# DummyLoad.net
KiCad netlist of a schematic drawn in EAGLE
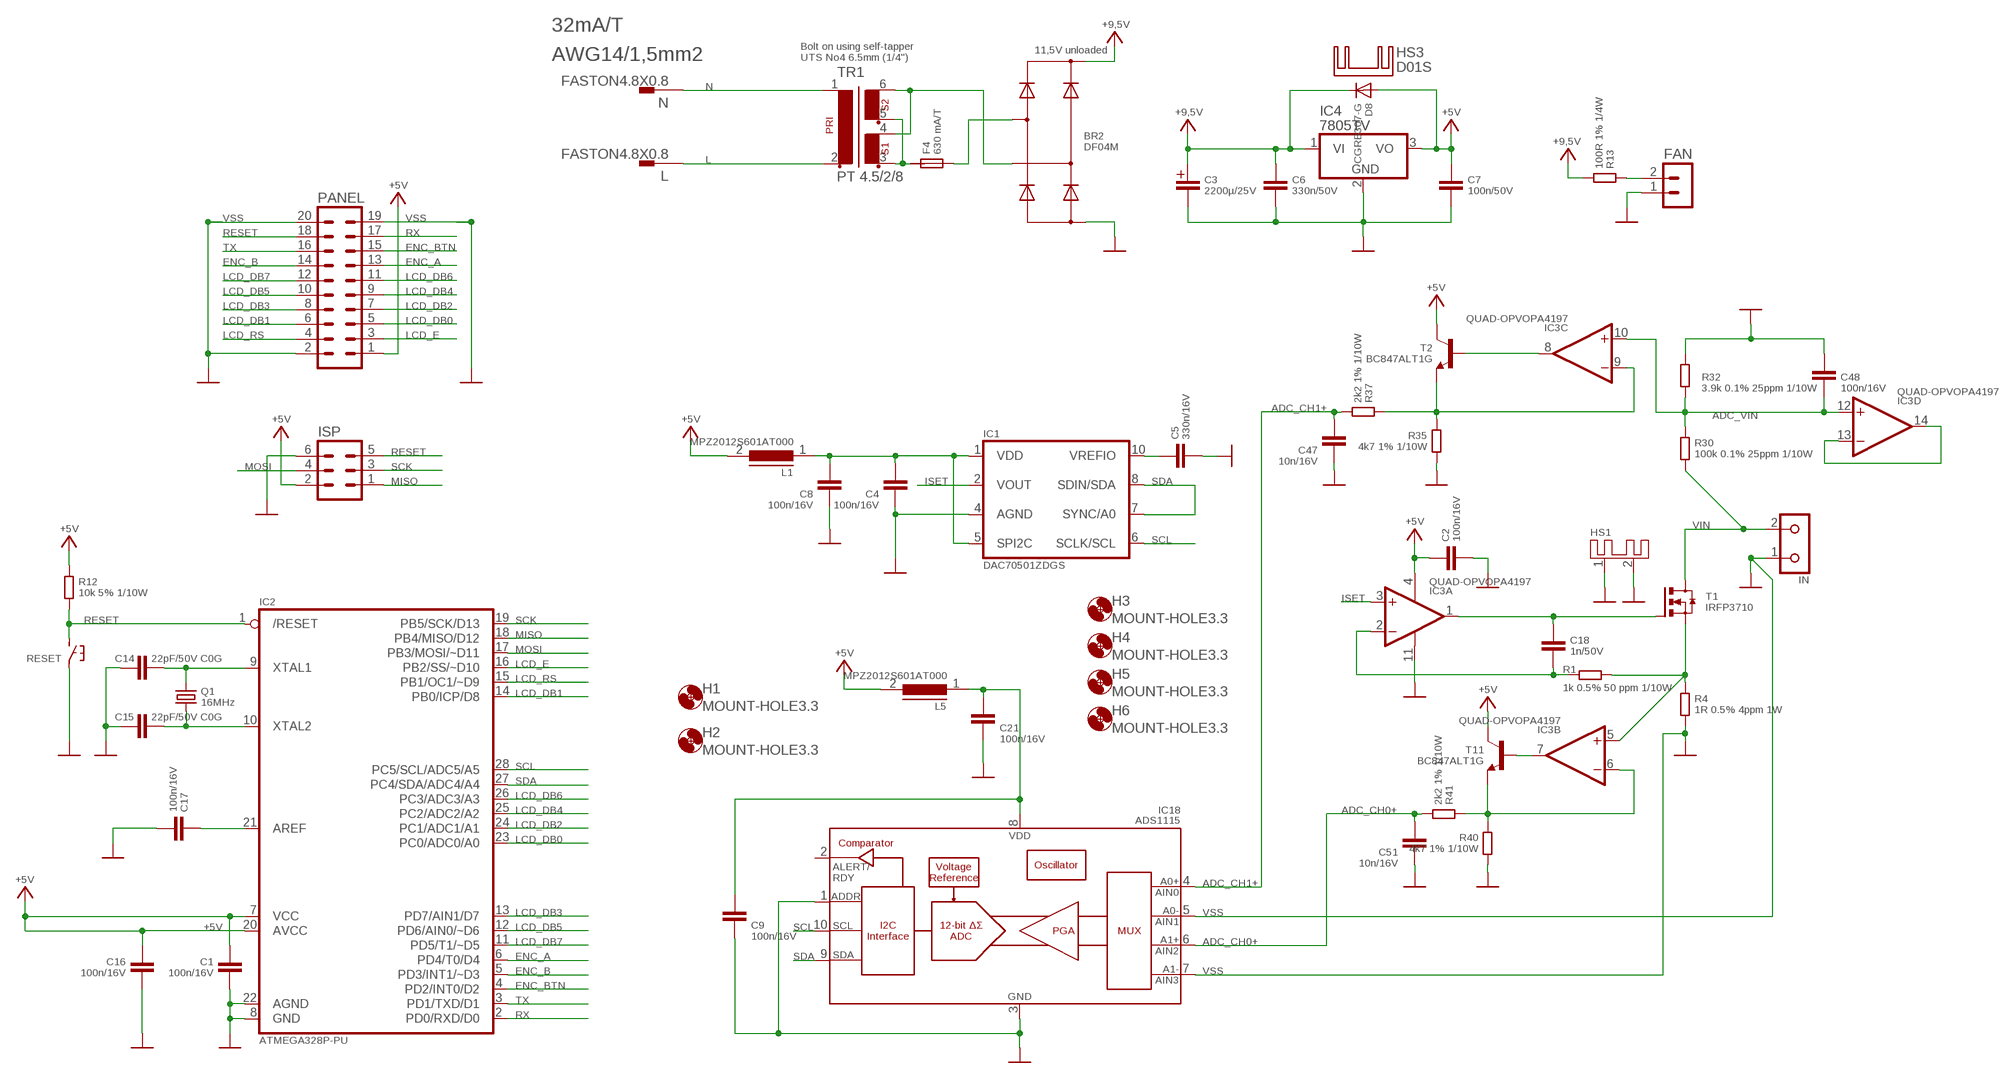
[diagram p0: schematic, sheet 1]

(export (version "E")
  (design (tool "Eeschema 10.0.6"))
  (components
    (comp (ref "BR2")
      (value "DF04M")
      (footprint "eagle-import:BR-DIL2")
      (libsource (lib "eagle-import") (part "BRDIL2"))
    )
    (comp (ref "C1")
      (value "100n/16V")
      (footprint "eagle-import:0805")
      (libsource (lib "eagle-import") (part "CC/0805"))
    )
    (comp (ref "C2")
      (value "100n/16V")
      (footprint "eagle-import:0805")
      (libsource (lib "eagle-import") (part "CC/0805"))
    )
    (comp (ref "C3")
      (value "2200µ/25V")
      (footprint "eagle-import:C+_5_12.5")
      (libsource (lib "eagle-import") (part "C+5/12.5"))
    )
    (comp (ref "C4")
      (value "100n/16V")
      (footprint "eagle-import:0805")
      (libsource (lib "eagle-import") (part "CC/0805"))
    )
    (comp (ref "C5")
      (value "330n/16V")
      (footprint "eagle-import:0805")
      (libsource (lib "eagle-import") (part "CC/0805"))
    )
    (comp (ref "C6")
      (value "330n/50V")
      (footprint "eagle-import:0805")
      (libsource (lib "eagle-import") (part "CC/0805"))
    )
    (comp (ref "C7")
      (value "100n/50V")
      (footprint "eagle-import:0805")
      (libsource (lib "eagle-import") (part "CC/0805"))
    )
    (comp (ref "C8")
      (value "100n/16V")
      (footprint "eagle-import:0805")
      (libsource (lib "eagle-import") (part "CC/0805"))
    )
    (comp (ref "C9")
      (value "100n/16V")
      (footprint "eagle-import:0805")
      (libsource (lib "eagle-import") (part "CC/0805"))
    )
    (comp (ref "C14")
      (value "22pF/50V C0G")
      (footprint "eagle-import:0805")
      (libsource (lib "eagle-import") (part "CC/0805"))
    )
    (comp (ref "C15")
      (value "22pF/50V C0G")
      (footprint "eagle-import:0805")
      (libsource (lib "eagle-import") (part "CC/0805"))
    )
    (comp (ref "C16")
      (value "100n/16V")
      (footprint "eagle-import:0805")
      (libsource (lib "eagle-import") (part "CC/0805"))
    )
    (comp (ref "C17")
      (value "100n/16V")
      (footprint "eagle-import:0805")
      (libsource (lib "eagle-import") (part "CC/0805"))
    )
    (comp (ref "C18")
      (value "1n/50V")
      (footprint "eagle-import:0805")
      (libsource (lib "eagle-import") (part "CC/0805"))
    )
    (comp (ref "C21")
      (value "100n/16V")
      (footprint "eagle-import:0805")
      (libsource (lib "eagle-import") (part "CC/0805"))
    )
    (comp (ref "C47")
      (value "10n/16V")
      (footprint "eagle-import:0805")
      (libsource (lib "eagle-import") (part "CC/0805"))
    )
    (comp (ref "C48")
      (value "100n/16V")
      (footprint "eagle-import:0805")
      (libsource (lib "eagle-import") (part "CC/0805"))
    )
    (comp (ref "C51")
      (value "10n/16V")
      (footprint "eagle-import:0805")
      (libsource (lib "eagle-import") (part "CC/0805"))
    )
    (comp (ref "D8")
      (value "CGRB307-G")
      (footprint "eagle-import:DO214AA-CGRB307-G")
      (libsource (lib "eagle-import") (part "DWIDE"))
    )
    (comp (ref "F4")
      (value "630 mA/T")
      (footprint "eagle-import:F5X20")
      (libsource (lib "eagle-import") (part "F5X20"))
    )
    (comp (ref "FAN")
      (value "JST-PH-2.0-2P")
      (footprint "eagle-import:JST-PH-2.0-2P")
      (libsource (lib "eagle-import") (part "JST-PH-2.0-2P"))
    )
    (comp (ref "H1")
      (value "MOUNT-HOLE3.3")
      (footprint "eagle-import:3,3")
      (libsource (lib "eagle-import") (part "MOUNT-HOLE3.3"))
    )
    (comp (ref "H2")
      (value "MOUNT-HOLE3.3")
      (footprint "eagle-import:3,3")
      (libsource (lib "eagle-import") (part "MOUNT-HOLE3.3"))
    )
    (comp (ref "H3")
      (value "MOUNT-HOLE3.3")
      (footprint "eagle-import:3,3")
      (libsource (lib "eagle-import") (part "MOUNT-HOLE3.3"))
    )
    (comp (ref "H4")
      (value "MOUNT-HOLE3.3")
      (footprint "eagle-import:3,3")
      (libsource (lib "eagle-import") (part "MOUNT-HOLE3.3"))
    )
    (comp (ref "H5")
      (value "MOUNT-HOLE3.3")
      (footprint "eagle-import:3,3")
      (libsource (lib "eagle-import") (part "MOUNT-HOLE3.3"))
    )
    (comp (ref "H6")
      (value "MOUNT-HOLE3.3")
      (footprint "eagle-import:3,3")
      (libsource (lib "eagle-import") (part "MOUNT-HOLE3.3"))
    )
    (comp (ref "HS1")
      (value "HSCR201-50")
      (footprint "eagle-import:CR201-50")
      (libsource (lib "eagle-import") (part "HSCR201-50"))
    )
    (comp (ref "HS3")
      (value "D01S")
      (footprint "eagle-import:D01S")
      (libsource (lib "eagle-import") (part "D01S"))
    )
    (comp (ref "IC1")
      (value "DAC70501ZDGS")
      (footprint "eagle-import:VSSOP10")
      (libsource (lib "eagle-import") (part "DAC70501"))
    )
    (comp (ref "IC2")
      (value "ATMEGA328P-PU")
      (footprint "eagle-import:DIL28")
      (libsource (lib "eagle-import") (part "ATMEGA328P-PU"))
    )
    (comp (ref "IC3")
      (value "QUAD-OPVOPA4197")
      (footprint "eagle-import:SO14")
      (fields (field (name "OC_MOUSER") "595-OPA4197IDR"))
      (libsource (lib "eagle-import") (part "QUAD-OPVOPA4197"))
    )
    (comp (ref "IC4")
      (value "7805TV")
      (footprint "eagle-import:TO220V")
      (libsource (lib "eagle-import") (part "78TV05"))
    )
    (comp (ref "IC18")
      (value "ADS1115")
      (footprint "eagle-import:VSSOP10")
      (libsource (lib "eagle-import") (part "ADS1015VSSOP10"))
    )
    (comp (ref "IN")
      (value "KL2691311500002")
      (footprint "eagle-import:KL2-691311500002")
      (libsource (lib "eagle-import") (part "KL2691311500002"))
    )
    (comp (ref "ISP")
      (value "ML6")
      (footprint "eagle-import:ML6")
      (libsource (lib "eagle-import") (part "ML6"))
    )
    (comp (ref "L")
      (value "FASTON4.8X0.8")
      (footprint "eagle-import:FASTON-4.8X0.8")
      (libsource (lib "eagle-import") (part "FASTON4.8X0.8"))
    )
    (comp (ref "L1")
      (value "MPZ2012S601AT000")
      (footprint "eagle-import:C0805K")
      (libsource (lib "eagle-import") (part "L0805"))
    )
    (comp (ref "L5")
      (value "MPZ2012S601AT000")
      (footprint "eagle-import:C0805K")
      (libsource (lib "eagle-import") (part "L0805"))
    )
    (comp (ref "N")
      (value "FASTON4.8X0.8")
      (footprint "eagle-import:FASTON-4.8X0.8")
      (libsource (lib "eagle-import") (part "FASTON4.8X0.8"))
    )
    (comp (ref "PANEL")
      (value "MA10-2")
      (footprint "eagle-import:MA10-2")
      (libsource (lib "eagle-import") (part "MA10-2"))
    )
    (comp (ref "Q1")
      (value "16MHz")
      (footprint "eagle-import:Q-5X3.2MM-TXC-7A.SERIES")
      (libsource (lib "eagle-import") (part "Q5X3.2MM-TXC-7A-SERIES"))
    )
    (comp (ref "R1")
      (value "1k 0.5% 50 ppm 1/10W")
      (footprint "eagle-import:C0805K")
      (libsource (lib "eagle-import") (part "R-SMD0805"))
    )
    (comp (ref "R4")
      (value "1R 0.5% 4ppm 1W")
      (footprint "eagle-import:R-SHUNT-VSR")
      (libsource (lib "eagle-import") (part "R-SHUNTVSR"))
    )
    (comp (ref "R12")
      (value "10k 5% 1/10W")
      (footprint "eagle-import:C0805K")
      (libsource (lib "eagle-import") (part "R-SMD0805"))
    )
    (comp (ref "R13")
      (value "100R 1% 1/4W")
      (footprint "eagle-import:C0805K")
      (libsource (lib "eagle-import") (part "R-SMD0805"))
    )
    (comp (ref "R30")
      (value "100k 0.1% 25ppm 1/10W")
      (footprint "eagle-import:C0805K")
      (libsource (lib "eagle-import") (part "R-SMD0805"))
    )
    (comp (ref "R32")
      (value "3.9k 0.1% 25ppm 1/10W")
      (footprint "eagle-import:C0805K")
      (libsource (lib "eagle-import") (part "R-SMD0805"))
    )
    (comp (ref "R35")
      (value "4k7 1% 1/10W")
      (footprint "eagle-import:C0805K")
      (libsource (lib "eagle-import") (part "R-SMD0805"))
    )
    (comp (ref "R37")
      (value "2k2 1% 1/10W")
      (footprint "eagle-import:C0805K")
      (libsource (lib "eagle-import") (part "R-SMD0805"))
    )
    (comp (ref "R40")
      (value "4k7 1% 1/10W")
      (footprint "eagle-import:C0805K")
      (libsource (lib "eagle-import") (part "R-SMD0805"))
    )
    (comp (ref "R41")
      (value "2k2 1% 1/10W")
      (footprint "eagle-import:C0805K")
      (libsource (lib "eagle-import") (part "R-SMD0805"))
    )
    (comp (ref "RESET")
      (value "TS1B3F-10XX")
      (footprint "eagle-import:B3F-10XX")
      (libsource (lib "eagle-import") (part "TS1B3F-10XX"))
    )
    (comp (ref "T1")
      (value "IRFP3710")
      (footprint "eagle-import:TOP3AV")
      (libsource (lib "eagle-import") (part "T-NMOSTO247"))
    )
    (comp (ref "T2")
      (value "BC847ALT1G")
      (footprint "eagle-import:SOT23-BEC")
      (libsource (lib "eagle-import") (part "T-NPNSOT23-BEC"))
    )
    (comp (ref "T11")
      (value "BC847ALT1G")
      (footprint "eagle-import:SOT23-BEC")
      (libsource (lib "eagle-import") (part "T-NPNSOT23-BEC"))
    )
    (comp (ref "TR1")
      (value "PT 4.5/2/8")
      (footprint "eagle-import:PT_4,5_2_..")
      (libsource (lib "eagle-import") (part "PT4,5/2/.."))
    )
  )
  (nets
    (net (code "1") (name "+5V") (class "Default")
      (node (ref "C1") (pin "1") (pinfunction "1_1") (pintype "passive"))
      (node (ref "C16") (pin "1") (pinfunction "1_1") (pintype "passive"))
      (node (ref "C2") (pin "1") (pinfunction "1_1") (pintype "passive"))
      (node (ref "C7") (pin "1") (pinfunction "1_1") (pintype "passive"))
      (node (ref "D8") (pin "A") (pinfunction "A_A") (pintype "passive"))
      (node (ref "IC2") (pin "20") (pinfunction "AVCC_20") (pintype "power_in"))
      (node (ref "IC2") (pin "7") (pinfunction "VCC_7") (pintype "power_in"))
      (node (ref "IC3") (pin "4") (pinfunction "V+_4") (pintype "power_in"))
      (node (ref "IC4") (pin "3") (pinfunction "VO_3") (pintype "passive"))
      (node (ref "ISP") (pin "2") (pinfunction "2_2") (pintype "passive"))
      (node (ref "L1") (pin "2") (pinfunction "2_2") (pintype "passive"))
      (node (ref "L5") (pin "2") (pinfunction "2_2") (pintype "passive"))
      (node (ref "PANEL") (pin "1") (pinfunction "1_1") (pintype "passive"))
      (node (ref "R12") (pin "1") (pinfunction "1_1") (pintype "passive"))
      (node (ref "T11") (pin "C") (pinfunction "C_C") (pintype "passive"))
      (node (ref "T2") (pin "C") (pinfunction "C_C") (pintype "passive"))
    )
    (net (code "2") (name "+9,5V") (class "Default")
      (node (ref "BR2") (pin "DC+") (pinfunction "DC+_DC+") (pintype "passive"))
      (node (ref "C3") (pin "+") (pinfunction "+_+") (pintype "passive"))
      (node (ref "C6") (pin "1") (pinfunction "1_1") (pintype "passive"))
      (node (ref "D8") (pin "C") (pinfunction "C_C") (pintype "passive"))
      (node (ref "IC4") (pin "1") (pinfunction "VI_1") (pintype "input"))
      (node (ref "R13") (pin "2") (pinfunction "2_2") (pintype "passive"))
    )
    (net (code "3") (name "/ADC_CH0+") (class "Default")
      (node (ref "C51") (pin "1") (pinfunction "1_1") (pintype "passive"))
      (node (ref "IC18") (pin "6") (pinfunction "AIN2_6") (pintype "bidirectional"))
      (node (ref "R41") (pin "2") (pinfunction "2_2") (pintype "passive"))
    )
    (net (code "4") (name "/ADC_CH1+") (class "Default")
      (node (ref "C47") (pin "1") (pinfunction "1_1") (pintype "passive"))
      (node (ref "IC18") (pin "4") (pinfunction "AIN0_4") (pintype "bidirectional"))
      (node (ref "R37") (pin "2") (pinfunction "2_2") (pintype "passive"))
    )
    (net (code "5") (name "/ADC_VIN") (class "Default")
      (node (ref "C48") (pin "2") (pinfunction "2_2") (pintype "passive"))
      (node (ref "IC3") (pin "10") (pinfunction "+IN_10") (pintype "input"))
      (node (ref "IC3") (pin "12") (pinfunction "+IN_12") (pintype "input"))
      (node (ref "R30") (pin "1") (pinfunction "1_1") (pintype "passive"))
      (node (ref "R32") (pin "2") (pinfunction "2_2") (pintype "passive"))
    )
    (net (code "6") (name "/ENC_A") (class "Default")
      (node (ref "IC2") (pin "6") (pinfunction "PD4/T0/D4_6") (pintype "bidirectional"))
      (node (ref "PANEL") (pin "13") (pinfunction "13_13") (pintype "passive"))
    )
    (net (code "7") (name "/ENC_B") (class "Default")
      (node (ref "IC2") (pin "5") (pinfunction "PD3/INT1/~{D3}_5") (pintype "bidirectional"))
      (node (ref "PANEL") (pin "14") (pinfunction "14_14") (pintype "passive"))
    )
    (net (code "8") (name "/ENC_BTN") (class "Default")
      (node (ref "IC2") (pin "4") (pinfunction "PD2/INT0/D2_4") (pintype "bidirectional"))
      (node (ref "PANEL") (pin "15") (pinfunction "15_15") (pintype "passive"))
    )
    (net (code "9") (name "/ISET") (class "Default")
      (node (ref "IC1") (pin "2") (pinfunction "VOUT_2") (pintype "output"))
      (node (ref "IC3") (pin "3") (pinfunction "+IN_3") (pintype "input"))
    )
    (net (code "10") (name "/L") (class "Default")
      (node (ref "L") (pin "A1") (pinfunction "1_A1") (pintype "passive"))
      (node (ref "L") (pin "A2") (pinfunction "1_A2") (pintype "passive"))
      (node (ref "TR1") (pin "2") (pinfunction "2_2") (pintype "passive"))
    )
    (net (code "11") (name "/LCD_DB0") (class "Default")
      (node (ref "IC2") (pin "23") (pinfunction "PC0/ADC0/A0_23") (pintype "bidirectional"))
      (node (ref "PANEL") (pin "5") (pinfunction "5_5") (pintype "passive"))
    )
    (net (code "12") (name "/LCD_DB1") (class "Default")
      (node (ref "IC2") (pin "14") (pinfunction "PB0/ICP/D8_14") (pintype "bidirectional"))
      (node (ref "PANEL") (pin "6") (pinfunction "6_6") (pintype "passive"))
    )
    (net (code "13") (name "/LCD_DB2") (class "Default")
      (node (ref "IC2") (pin "24") (pinfunction "PC1/ADC1/A1_24") (pintype "bidirectional"))
      (node (ref "PANEL") (pin "7") (pinfunction "7_7") (pintype "passive"))
    )
    (net (code "14") (name "/LCD_DB3") (class "Default")
      (node (ref "IC2") (pin "13") (pinfunction "PD7/AIN1/D7_13") (pintype "bidirectional"))
      (node (ref "PANEL") (pin "8") (pinfunction "8_8") (pintype "passive"))
    )
    (net (code "15") (name "/LCD_DB4") (class "Default")
      (node (ref "IC2") (pin "25") (pinfunction "PC2/ADC2/A2_25") (pintype "bidirectional"))
      (node (ref "PANEL") (pin "9") (pinfunction "9_9") (pintype "passive"))
    )
    (net (code "16") (name "/LCD_DB5") (class "Default")
      (node (ref "IC2") (pin "12") (pinfunction "PD6/AIN0/~{D6}_12") (pintype "bidirectional"))
      (node (ref "PANEL") (pin "10") (pinfunction "10_10") (pintype "passive"))
    )
    (net (code "17") (name "/LCD_DB6") (class "Default")
      (node (ref "IC2") (pin "26") (pinfunction "PC3/ADC3/A3_26") (pintype "bidirectional"))
      (node (ref "PANEL") (pin "11") (pinfunction "11_11") (pintype "passive"))
    )
    (net (code "18") (name "/LCD_DB7") (class "Default")
      (node (ref "IC2") (pin "11") (pinfunction "PD5/T1/~{D5}_11") (pintype "bidirectional"))
      (node (ref "PANEL") (pin "12") (pinfunction "12_12") (pintype "passive"))
    )
    (net (code "19") (name "/LCD_E") (class "Default")
      (node (ref "IC2") (pin "16") (pinfunction "PB2/SS/~{D10}_16") (pintype "bidirectional"))
      (node (ref "PANEL") (pin "3") (pinfunction "3_3") (pintype "passive"))
    )
    (net (code "20") (name "/LCD_RS") (class "Default")
      (node (ref "IC2") (pin "15") (pinfunction "PB1/OC1/~{D9}_15") (pintype "bidirectional"))
      (node (ref "PANEL") (pin "4") (pinfunction "4_4") (pintype "passive"))
    )
    (net (code "21") (name "/MISO") (class "Default")
      (node (ref "IC2") (pin "18") (pinfunction "PB4/MISO/D12_18") (pintype "bidirectional"))
      (node (ref "ISP") (pin "1") (pinfunction "1_1") (pintype "passive"))
    )
    (net (code "22") (name "/MOSI") (class "Default")
      (node (ref "IC2") (pin "17") (pinfunction "PB3/MOSI/~{D11}_17") (pintype "bidirectional"))
      (node (ref "ISP") (pin "4") (pinfunction "4_4") (pintype "passive"))
    )
    (net (code "23") (name "/N") (class "Default")
      (node (ref "N") (pin "A1") (pinfunction "1_A1") (pintype "passive"))
      (node (ref "N") (pin "A2") (pinfunction "1_A2") (pintype "passive"))
      (node (ref "TR1") (pin "1") (pinfunction "1_1") (pintype "passive"))
    )
    (net (code "24") (name "/RESET") (class "Default")
      (node (ref "IC2") (pin "1") (pinfunction "/RESET_1") (pintype "input"))
      (node (ref "ISP") (pin "5") (pinfunction "5_5") (pintype "passive"))
      (node (ref "PANEL") (pin "18") (pinfunction "18_18") (pintype "passive"))
      (node (ref "R12") (pin "2") (pinfunction "2_2") (pintype "passive"))
      (node (ref "RESET") (pin "3") (pinfunction "2_3") (pintype "passive"))
    )
    (net (code "25") (name "/RX") (class "Default")
      (node (ref "IC2") (pin "2") (pinfunction "PD0/RXD/D0_2") (pintype "bidirectional"))
      (node (ref "PANEL") (pin "17") (pinfunction "17_17") (pintype "passive"))
    )
    (net (code "26") (name "/SCK") (class "Default")
      (node (ref "IC2") (pin "19") (pinfunction "PB5/SCK/D13_19") (pintype "bidirectional"))
      (node (ref "ISP") (pin "3") (pinfunction "3_3") (pintype "passive"))
    )
    (net (code "27") (name "/SCL") (class "Default")
      (node (ref "IC1") (pin "6") (pinfunction "SCLK/SCL_6") (pintype "input"))
      (node (ref "IC18") (pin "10") (pinfunction "SCL_10") (pintype "bidirectional"))
      (node (ref "IC2") (pin "28") (pinfunction "PC5/SCL/ADC5/A5_28") (pintype "bidirectional"))
    )
    (net (code "28") (name "/SDA") (class "Default")
      (node (ref "IC1") (pin "7") (pinfunction "SYNC/A0_7") (pintype "input"))
      (node (ref "IC1") (pin "8") (pinfunction "SDIN/SDA_8") (pintype "input"))
      (node (ref "IC18") (pin "9") (pinfunction "SDA_9") (pintype "bidirectional"))
      (node (ref "IC2") (pin "27") (pinfunction "PC4/SDA/ADC4/A4_27") (pintype "bidirectional"))
    )
    (net (code "29") (name "/TX") (class "Default")
      (node (ref "IC2") (pin "3") (pinfunction "PD1/TXD/D1_3") (pintype "bidirectional"))
      (node (ref "PANEL") (pin "16") (pinfunction "16_16") (pintype "passive"))
    )
    (net (code "30") (name "/VIN") (class "Default")
      (node (ref "IN") (pin "2") (pinfunction "2_2") (pintype "passive"))
      (node (ref "R30") (pin "2") (pinfunction "2_2") (pintype "passive"))
      (node (ref "T1") (pin "C") (pinfunction "D_C") (pintype "passive"))
    )
    (net (code "31") (name "Net-(BR2-PadAC1)") (class "Default")
      (node (ref "BR2") (pin "AC1") (pinfunction "AC1_AC1") (pintype "passive"))
      (node (ref "F4") (pin "3") (pinfunction "2_3") (pintype "passive"))
      (node (ref "F4") (pin "4") (pinfunction "2_4") (pintype "passive"))
    )
    (net (code "32") (name "Net-(BR2-PadAC2)") (class "Default")
      (node (ref "BR2") (pin "AC2") (pinfunction "AC2_AC2") (pintype "passive"))
      (node (ref "TR1") (pin "4") (pinfunction "4_4") (pintype "passive"))
      (node (ref "TR1") (pin "6") (pinfunction "6_6") (pintype "passive"))
    )
    (net (code "33") (name "Net-(F4-1-Pad2)") (class "Default")
      (node (ref "F4") (pin "1") (pinfunction "1_1") (pintype "passive"))
      (node (ref "F4") (pin "2") (pinfunction "1_2") (pintype "passive"))
      (node (ref "TR1") (pin "3") (pinfunction "3_3") (pintype "passive"))
      (node (ref "TR1") (pin "5") (pinfunction "5_5") (pintype "passive"))
    )
    (net (code "34") (name "Net-(FAN-Pad2)") (class "Default")
      (node (ref "FAN") (pin "2") (pinfunction "2_2") (pintype "passive"))
      (node (ref "R13") (pin "1") (pinfunction "1_1") (pintype "passive"))
    )
    (net (code "35") (name "Net-(IC1-SPI2C)") (class "Default")
      (node (ref "C4") (pin "1") (pinfunction "1_1") (pintype "passive"))
      (node (ref "C8") (pin "1") (pinfunction "1_1") (pintype "passive"))
      (node (ref "IC1") (pin "1") (pinfunction "VDD_1") (pintype "power_in"))
      (node (ref "IC1") (pin "5") (pinfunction "SPI2C_5") (pintype "bidirectional"))
      (node (ref "L1") (pin "1") (pinfunction "1_1") (pintype "passive"))
    )
    (net (code "36") (name "Net-(IC1-VREFIO)") (class "Default")
      (node (ref "C5") (pin "1") (pinfunction "1_1") (pintype "passive"))
      (node (ref "IC1") (pin "10") (pinfunction "VREFIO_10") (pintype "bidirectional"))
    )
    (net (code "37") (name "Net-(IC2-AREF)") (class "Default")
      (node (ref "C17") (pin "1") (pinfunction "1_1") (pintype "passive"))
      (node (ref "IC2") (pin "21") (pinfunction "AREF_21") (pintype "passive"))
    )
    (net (code "38") (name "Net-(IC2-XTAL1)") (class "Default")
      (node (ref "C14") (pin "2") (pinfunction "2_2") (pintype "passive"))
      (node (ref "IC2") (pin "9") (pinfunction "XTAL1_9") (pintype "passive"))
      (node (ref "Q1") (pin "2") (pinfunction "2_2") (pintype "passive"))
    )
    (net (code "39") (name "Net-(IC2-XTAL2)") (class "Default")
      (node (ref "C15") (pin "2") (pinfunction "2_2") (pintype "passive"))
      (node (ref "IC2") (pin "10") (pinfunction "XTAL2_10") (pintype "passive"))
      (node (ref "Q1") (pin "1") (pinfunction "1_1") (pintype "passive"))
    )
    (net (code "40") (name "Net-(IC3A--IN)") (class "Default")
      (node (ref "C18") (pin "2") (pinfunction "2_2") (pintype "passive"))
      (node (ref "IC3") (pin "2") (pinfunction "-IN_2") (pintype "input"))
      (node (ref "R1") (pin "2") (pinfunction "2_2") (pintype "passive"))
    )
    (net (code "41") (name "Net-(IC3A-OUT)") (class "Default")
      (node (ref "C18") (pin "1") (pinfunction "1_1") (pintype "passive"))
      (node (ref "IC3") (pin "1") (pinfunction "OUT_1") (pintype "output"))
      (node (ref "T1") (pin "B") (pinfunction "G_B") (pintype "passive"))
    )
    (net (code "42") (name "Net-(IC3B-+IN)") (class "Default")
      (node (ref "IC3") (pin "5") (pinfunction "+IN_5") (pintype "input"))
      (node (ref "R1") (pin "1") (pinfunction "1_1") (pintype "passive"))
      (node (ref "R4") (pin "1") (pinfunction "1_1") (pintype "passive"))
      (node (ref "T1") (pin "E") (pinfunction "S_E") (pintype "passive"))
    )
    (net (code "43") (name "Net-(IC3B--IN)") (class "Default")
      (node (ref "IC3") (pin "6") (pinfunction "-IN_6") (pintype "input"))
      (node (ref "R40") (pin "1") (pinfunction "1_1") (pintype "passive"))
      (node (ref "R41") (pin "1") (pinfunction "1_1") (pintype "passive"))
      (node (ref "T11") (pin "E") (pinfunction "E_E") (pintype "passive"))
    )
    (net (code "44") (name "Net-(IC3B-OUT)") (class "Default")
      (node (ref "IC3") (pin "7") (pinfunction "OUT_7") (pintype "output"))
      (node (ref "T11") (pin "B") (pinfunction "B_B") (pintype "passive"))
    )
    (net (code "45") (name "Net-(IC3C--IN)") (class "Default")
      (node (ref "IC3") (pin "9") (pinfunction "-IN_9") (pintype "input"))
      (node (ref "R35") (pin "1") (pinfunction "1_1") (pintype "passive"))
      (node (ref "R37") (pin "1") (pinfunction "1_1") (pintype "passive"))
      (node (ref "T2") (pin "E") (pinfunction "E_E") (pintype "passive"))
    )
    (net (code "46") (name "Net-(IC3C-OUT)") (class "Default")
      (node (ref "IC3") (pin "8") (pinfunction "OUT_8") (pintype "output"))
      (node (ref "T2") (pin "B") (pinfunction "B_B") (pintype "passive"))
    )
    (net (code "47") (name "Net-(IC3D--IN)") (class "Default")
      (node (ref "IC3") (pin "13") (pinfunction "-IN_13") (pintype "input"))
      (node (ref "IC3") (pin "14") (pinfunction "OUT_14") (pintype "output"))
    )
    (net (code "48") (name "Net-(IC18-VDD)") (class "Default")
      (node (ref "C21") (pin "1") (pinfunction "1_1") (pintype "passive"))
      (node (ref "C9") (pin "1") (pinfunction "1_1") (pintype "passive"))
      (node (ref "IC18") (pin "8") (pinfunction "VDD_8") (pintype "bidirectional"))
      (node (ref "L5") (pin "1") (pinfunction "1_1") (pintype "passive"))
    )
    (net (code "49") (name "VSS") (class "Default")
      (node (ref "BR2") (pin "DC-") (pinfunction "DC-_DC-") (pintype "passive"))
      (node (ref "C1") (pin "2") (pinfunction "2_2") (pintype "passive"))
      (node (ref "C14") (pin "1") (pinfunction "1_1") (pintype "passive"))
      (node (ref "C15") (pin "1") (pinfunction "1_1") (pintype "passive"))
      (node (ref "C16") (pin "2") (pinfunction "2_2") (pintype "passive"))
      (node (ref "C17") (pin "2") (pinfunction "2_2") (pintype "passive"))
      (node (ref "C2") (pin "2") (pinfunction "2_2") (pintype "passive"))
      (node (ref "C21") (pin "2") (pinfunction "2_2") (pintype "passive"))
      (node (ref "C3") (pin "-") (pinfunction "-_-") (pintype "passive"))
      (node (ref "C4") (pin "2") (pinfunction "2_2") (pintype "passive"))
      (node (ref "C47") (pin "2") (pinfunction "2_2") (pintype "passive"))
      (node (ref "C48") (pin "1") (pinfunction "1_1") (pintype "passive"))
      (node (ref "C5") (pin "2") (pinfunction "2_2") (pintype "passive"))
      (node (ref "C51") (pin "2") (pinfunction "2_2") (pintype "passive"))
      (node (ref "C6") (pin "2") (pinfunction "2_2") (pintype "passive"))
      (node (ref "C7") (pin "2") (pinfunction "2_2") (pintype "passive"))
      (node (ref "C8") (pin "2") (pinfunction "2_2") (pintype "passive"))
      (node (ref "C9") (pin "2") (pinfunction "2_2") (pintype "passive"))
      (node (ref "FAN") (pin "1") (pinfunction "1_1") (pintype "passive"))
      (node (ref "HS1") (pin "1") (pinfunction "1_1") (pintype "passive"))
      (node (ref "HS1") (pin "2") (pinfunction "2_2") (pintype "passive"))
      (node (ref "IC1") (pin "4") (pinfunction "AGND_4") (pintype "power_in"))
      (node (ref "IC18") (pin "1") (pinfunction "ADDR_1") (pintype "bidirectional"))
      (node (ref "IC18") (pin "3") (pinfunction "VSS_3") (pintype "bidirectional"))
      (node (ref "IC18") (pin "5") (pinfunction "AIN1_5") (pintype "bidirectional"))
      (node (ref "IC18") (pin "7") (pinfunction "AIN3_7") (pintype "bidirectional"))
      (node (ref "IC2") (pin "22") (pinfunction "AGND_22") (pintype "power_in"))
      (node (ref "IC2") (pin "8") (pinfunction "GND_8") (pintype "power_in"))
      (node (ref "IC3") (pin "11") (pinfunction "V-_11") (pintype "power_in"))
      (node (ref "IC4") (pin "2") (pinfunction "GND_2") (pintype "passive"))
      (node (ref "IN") (pin "1") (pinfunction "1_1") (pintype "passive"))
      (node (ref "ISP") (pin "6") (pinfunction "6_6") (pintype "passive"))
      (node (ref "PANEL") (pin "19") (pinfunction "19_19") (pintype "passive"))
      (node (ref "PANEL") (pin "2") (pinfunction "2_2") (pintype "passive"))
      (node (ref "PANEL") (pin "20") (pinfunction "20_20") (pintype "passive"))
      (node (ref "R32") (pin "1") (pinfunction "1_1") (pintype "passive"))
      (node (ref "R35") (pin "2") (pinfunction "2_2") (pintype "passive"))
      (node (ref "R4") (pin "2") (pinfunction "2_2") (pintype "passive"))
      (node (ref "R40") (pin "2") (pinfunction "2_2") (pintype "passive"))
      (node (ref "RESET") (pin "1") (pinfunction "1_1") (pintype "passive"))
    )
    (net (code "50") (name "unconnected-(IC18-ALERT{slash}RDY-Pad2)") (class "Default")
      (node (ref "IC18") (pin "2") (pinfunction "ALERT/RDY_2") (pintype "bidirectional"))
    )
  )
)
